# Main.net
KiCad netlist of a schematic drawn in EAGLE
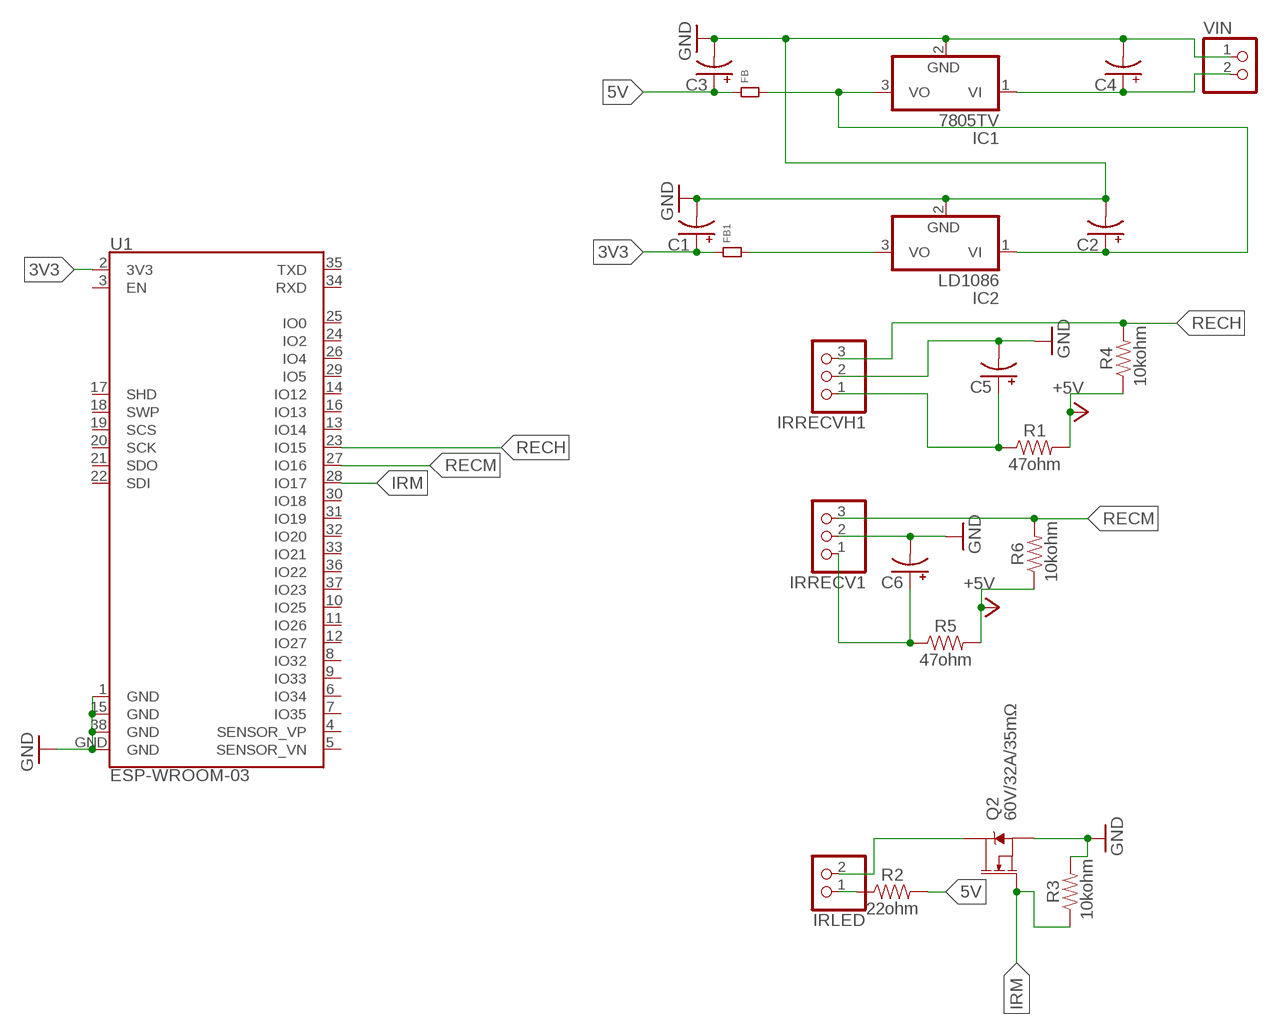
[diagram p0: schematic, sheet 1]

(export (version "E")
  (design (tool "Eeschema 10.0.6"))
  (components
    (comp (ref "C1")
      (value "CPOL-USE2-5")
      (footprint "eagle-import:E2-5")
      (libsource (lib "eagle-import") (part "CPOL-USE2-5"))
    )
    (comp (ref "C2")
      (value "CPOL-USE2-5")
      (footprint "eagle-import:E2-5")
      (libsource (lib "eagle-import") (part "CPOL-USE2-5"))
    )
    (comp (ref "C3")
      (value "CPOL-USE2-5")
      (footprint "eagle-import:E2-5")
      (libsource (lib "eagle-import") (part "CPOL-USE2-5"))
    )
    (comp (ref "C4")
      (value "CPOL-USE2-5")
      (footprint "eagle-import:E2-5")
      (libsource (lib "eagle-import") (part "CPOL-USE2-5"))
    )
    (comp (ref "C5")
      (value "CPOL-USE2-5")
      (footprint "eagle-import:E2-5")
      (libsource (lib "eagle-import") (part "CPOL-USE2-5"))
    )
    (comp (ref "C6")
      (value "CPOL-USE2-5")
      (footprint "eagle-import:E2-5")
      (libsource (lib "eagle-import") (part "CPOL-USE2-5"))
    )
    (comp (ref "FB")
      (value "RESISTOR.0603")
      (footprint "eagle-import:0603")
      (libsource (lib "eagle-import") (part "RESISTOR.0603"))
    )
    (comp (ref "FB1")
      (value "RESISTOR.0603")
      (footprint "eagle-import:0603")
      (libsource (lib "eagle-import") (part "RESISTOR.0603"))
    )
    (comp (ref "IC1")
      (value "7805TV")
      (footprint "eagle-import:TO220V")
      (libsource (lib "eagle-import") (part "78TV05"))
    )
    (comp (ref "IC2")
      (value "LD1086")
      (footprint "eagle-import:TO220V")
      (libsource (lib "eagle-import") (part "78TV05"))
    )
    (comp (ref "IRLED")
      (value "PINHD-1X2")
      (footprint "eagle-import:1X02")
      (libsource (lib "eagle-import") (part "PINHD-1X2"))
    )
    (comp (ref "IRRECV1")
      (value "PINHD-1X3")
      (footprint "eagle-import:1X03")
      (libsource (lib "eagle-import") (part "PINHD-1X3"))
    )
    (comp (ref "IRRECVH1")
      (value "PINHD-1X3")
      (footprint "eagle-import:1X03")
      (libsource (lib "eagle-import") (part "PINHD-1X3"))
    )
    (comp (ref "Q2")
      (value "60V/32A/35mΩ")
      (footprint "eagle-import:TO220V")
      (libsource (lib "eagle-import") (part "MOSFET-NCH-FQP30N06L"))
    )
    (comp (ref "R1")
      (value "47ohm")
      (footprint "eagle-import:AXIAL-0.3")
      (libsource (lib "eagle-import") (part "RESISTORAXIAL-0.3"))
    )
    (comp (ref "R2")
      (value "22ohm")
      (footprint "eagle-import:AXIAL-0.3")
      (libsource (lib "eagle-import") (part "RESISTORAXIAL-0.3"))
    )
    (comp (ref "R3")
      (value "10kohm")
      (footprint "eagle-import:AXIAL-0.3")
      (libsource (lib "eagle-import") (part "RESISTORAXIAL-0.3"))
    )
    (comp (ref "R4")
      (value "10kohm")
      (footprint "eagle-import:AXIAL-0.3")
      (libsource (lib "eagle-import") (part "RESISTORAXIAL-0.3"))
    )
    (comp (ref "R5")
      (value "47ohm")
      (footprint "eagle-import:AXIAL-0.3")
      (libsource (lib "eagle-import") (part "RESISTORAXIAL-0.3"))
    )
    (comp (ref "R6")
      (value "10kohm")
      (footprint "eagle-import:AXIAL-0.3")
      (libsource (lib "eagle-import") (part "RESISTORAXIAL-0.3"))
    )
    (comp (ref "U1")
      (value "ESP-WROOM-03")
      (footprint "eagle-import:ESP-WROOM-03")
      (libsource (lib "eagle-import") (part "ESP-WROOM-03"))
    )
    (comp (ref "VIN")
      (value "PINHD-1X2")
      (footprint "eagle-import:1X02")
      (libsource (lib "eagle-import") (part "PINHD-1X2"))
    )
  )
  (nets
    (net (code "1") (name "+5V") (class "Default")
      (node (ref "R1") (pin "P$2") (pinfunction "2_P$2") (pintype "passive"))
      (node (ref "R4") (pin "P$1") (pinfunction "1_P$1") (pintype "passive"))
      (node (ref "R5") (pin "P$2") (pinfunction "2_P$2") (pintype "passive"))
      (node (ref "R6") (pin "P$1") (pinfunction "1_P$1") (pintype "passive"))
    )
    (net (code "2") (name "3V3") (class "Default")
      (node (ref "C1") (pin "+") (pinfunction "+_+") (pintype "passive"))
      (node (ref "FB1") (pin "1") (pinfunction "1_1") (pintype "bidirectional"))
      (node (ref "U1") (pin "2") (pinfunction "3V3_2") (pintype "bidirectional"))
    )
    (net (code "3") (name "5V") (class "Default")
      (node (ref "C3") (pin "+") (pinfunction "+_+") (pintype "passive"))
      (node (ref "FB") (pin "1") (pinfunction "1_1") (pintype "bidirectional"))
      (node (ref "R2") (pin "P$2") (pinfunction "2_P$2") (pintype "passive"))
    )
    (net (code "4") (name "GND") (class "Default")
      (node (ref "C1") (pin "-") (pinfunction "-_-") (pintype "passive"))
      (node (ref "C2") (pin "-") (pinfunction "-_-") (pintype "passive"))
      (node (ref "C3") (pin "-") (pinfunction "-_-") (pintype "passive"))
      (node (ref "C4") (pin "-") (pinfunction "-_-") (pintype "passive"))
      (node (ref "C5") (pin "-") (pinfunction "-_-") (pintype "passive"))
      (node (ref "C6") (pin "-") (pinfunction "-_-") (pintype "passive"))
      (node (ref "IC1") (pin "2") (pinfunction "GND_2") (pintype "passive"))
      (node (ref "IC2") (pin "2") (pinfunction "GND_2") (pintype "passive"))
      (node (ref "IRRECV1") (pin "2") (pinfunction "2_2") (pintype "passive"))
      (node (ref "IRRECVH1") (pin "2") (pinfunction "2_2") (pintype "passive"))
      (node (ref "Q2") (pin "3") (pinfunction "S_3") (pintype "bidirectional"))
      (node (ref "R3") (pin "P$2") (pinfunction "2_P$2") (pintype "passive"))
      (node (ref "U1") (pin "1") (pinfunction "GND_1") (pintype "bidirectional"))
      (node (ref "U1") (pin "15") (pinfunction "GND_15") (pintype "bidirectional"))
      (node (ref "U1") (pin "38") (pinfunction "GND_38") (pintype "bidirectional"))
      (node (ref "U1") (pin "GND") (pinfunction "GND_GND") (pintype "bidirectional"))
      (node (ref "VIN") (pin "1") (pinfunction "1_1") (pintype "passive"))
    )
    (net (code "5") (name "IRM") (class "Default")
      (node (ref "Q2") (pin "1") (pinfunction "G_1") (pintype "bidirectional"))
      (node (ref "R3") (pin "P$1") (pinfunction "1_P$1") (pintype "passive"))
      (node (ref "U1") (pin "28") (pinfunction "IO17_28") (pintype "bidirectional"))
    )
    (net (code "6") (name "Net-(IC1-VI)") (class "Default")
      (node (ref "C4") (pin "+") (pinfunction "+_+") (pintype "passive"))
      (node (ref "IC1") (pin "1") (pinfunction "VI_1") (pintype "input"))
      (node (ref "VIN") (pin "2") (pinfunction "2_2") (pintype "passive"))
    )
    (net (code "7") (name "Net-(IC1-VO)") (class "Default")
      (node (ref "C2") (pin "+") (pinfunction "+_+") (pintype "passive"))
      (node (ref "FB") (pin "2") (pinfunction "2_2") (pintype "bidirectional"))
      (node (ref "IC1") (pin "3") (pinfunction "VO_3") (pintype "passive"))
      (node (ref "IC2") (pin "1") (pinfunction "VI_1") (pintype "input"))
    )
    (net (code "8") (name "Net-(IC2-VO)") (class "Default")
      (node (ref "FB1") (pin "2") (pinfunction "2_2") (pintype "bidirectional"))
      (node (ref "IC2") (pin "3") (pinfunction "VO_3") (pintype "passive"))
    )
    (net (code "9") (name "Net-(Q2-D)") (class "Default")
      (node (ref "IRLED") (pin "2") (pinfunction "2_2") (pintype "passive"))
      (node (ref "Q2") (pin "2") (pinfunction "D_2") (pintype "bidirectional"))
    )
    (net (code "10") (name "Net-(R1-1)") (class "Default")
      (node (ref "C5") (pin "+") (pinfunction "+_+") (pintype "passive"))
      (node (ref "IRRECVH1") (pin "1") (pinfunction "1_1") (pintype "passive"))
      (node (ref "R1") (pin "P$1") (pinfunction "1_P$1") (pintype "passive"))
    )
    (net (code "11") (name "Net-(R2-1)") (class "Default")
      (node (ref "IRLED") (pin "1") (pinfunction "1_1") (pintype "passive"))
      (node (ref "R2") (pin "P$1") (pinfunction "1_P$1") (pintype "passive"))
    )
    (net (code "12") (name "Net-(R5-1)") (class "Default")
      (node (ref "C6") (pin "+") (pinfunction "+_+") (pintype "passive"))
      (node (ref "IRRECV1") (pin "1") (pinfunction "1_1") (pintype "passive"))
      (node (ref "R5") (pin "P$1") (pinfunction "1_P$1") (pintype "passive"))
    )
    (net (code "13") (name "RECH") (class "Default")
      (node (ref "IRRECVH1") (pin "3") (pinfunction "3_3") (pintype "passive"))
      (node (ref "R4") (pin "P$2") (pinfunction "2_P$2") (pintype "passive"))
      (node (ref "U1") (pin "23") (pinfunction "IO15_23") (pintype "bidirectional"))
    )
    (net (code "14") (name "RECM") (class "Default")
      (node (ref "IRRECV1") (pin "3") (pinfunction "3_3") (pintype "passive"))
      (node (ref "R6") (pin "P$2") (pinfunction "2_P$2") (pintype "passive"))
      (node (ref "U1") (pin "27") (pinfunction "IO16_27") (pintype "bidirectional"))
    )
    (net (code "15") (name "unconnected-(U1-EN-Pad3)") (class "Default")
      (node (ref "U1") (pin "3") (pinfunction "EN_3") (pintype "bidirectional"))
    )
    (net (code "16") (name "unconnected-(U1-IO0-Pad25)") (class "Default")
      (node (ref "U1") (pin "25") (pinfunction "IO0_25") (pintype "bidirectional"))
    )
    (net (code "17") (name "unconnected-(U1-IO2-Pad24)") (class "Default")
      (node (ref "U1") (pin "24") (pinfunction "IO2_24") (pintype "bidirectional"))
    )
    (net (code "18") (name "unconnected-(U1-IO4-Pad26)") (class "Default")
      (node (ref "U1") (pin "26") (pinfunction "IO4_26") (pintype "bidirectional"))
    )
    (net (code "19") (name "unconnected-(U1-IO5-Pad29)") (class "Default")
      (node (ref "U1") (pin "29") (pinfunction "IO5_29") (pintype "bidirectional"))
    )
    (net (code "20") (name "unconnected-(U1-IO12-Pad14)") (class "Default")
      (node (ref "U1") (pin "14") (pinfunction "IO12_14") (pintype "bidirectional"))
    )
    (net (code "21") (name "unconnected-(U1-IO13-Pad16)") (class "Default")
      (node (ref "U1") (pin "16") (pinfunction "IO13_16") (pintype "bidirectional"))
    )
    (net (code "22") (name "unconnected-(U1-IO14-Pad13)") (class "Default")
      (node (ref "U1") (pin "13") (pinfunction "IO14_13") (pintype "bidirectional"))
    )
    (net (code "23") (name "unconnected-(U1-IO18-Pad30)") (class "Default")
      (node (ref "U1") (pin "30") (pinfunction "IO18_30") (pintype "bidirectional"))
    )
    (net (code "24") (name "unconnected-(U1-IO19-Pad31)") (class "Default")
      (node (ref "U1") (pin "31") (pinfunction "IO19_31") (pintype "bidirectional"))
    )
    (net (code "25") (name "unconnected-(U1-IO20-Pad32)") (class "Default")
      (node (ref "U1") (pin "32") (pinfunction "IO20_32") (pintype "bidirectional"))
    )
    (net (code "26") (name "unconnected-(U1-IO21-Pad33)") (class "Default")
      (node (ref "U1") (pin "33") (pinfunction "IO21_33") (pintype "bidirectional"))
    )
    (net (code "27") (name "unconnected-(U1-IO22-Pad36)") (class "Default")
      (node (ref "U1") (pin "36") (pinfunction "IO22_36") (pintype "bidirectional"))
    )
    (net (code "28") (name "unconnected-(U1-IO23-Pad37)") (class "Default")
      (node (ref "U1") (pin "37") (pinfunction "IO23_37") (pintype "bidirectional"))
    )
    (net (code "29") (name "unconnected-(U1-IO25-Pad10)") (class "Default")
      (node (ref "U1") (pin "10") (pinfunction "IO25_10") (pintype "bidirectional"))
    )
    (net (code "30") (name "unconnected-(U1-IO26-Pad11)") (class "Default")
      (node (ref "U1") (pin "11") (pinfunction "IO26_11") (pintype "bidirectional"))
    )
    (net (code "31") (name "unconnected-(U1-IO27-Pad12)") (class "Default")
      (node (ref "U1") (pin "12") (pinfunction "IO27_12") (pintype "bidirectional"))
    )
    (net (code "32") (name "unconnected-(U1-IO32-Pad8)") (class "Default")
      (node (ref "U1") (pin "8") (pinfunction "IO32_8") (pintype "bidirectional"))
    )
    (net (code "33") (name "unconnected-(U1-IO33-Pad9)") (class "Default")
      (node (ref "U1") (pin "9") (pinfunction "IO33_9") (pintype "bidirectional"))
    )
    (net (code "34") (name "unconnected-(U1-IO34-Pad6)") (class "Default")
      (node (ref "U1") (pin "6") (pinfunction "IO34_6") (pintype "bidirectional"))
    )
    (net (code "35") (name "unconnected-(U1-IO35-Pad7)") (class "Default")
      (node (ref "U1") (pin "7") (pinfunction "IO35_7") (pintype "bidirectional"))
    )
    (net (code "36") (name "unconnected-(U1-RXD-Pad34)") (class "Default")
      (node (ref "U1") (pin "34") (pinfunction "RXD_34") (pintype "bidirectional"))
    )
    (net (code "37") (name "unconnected-(U1-SCK-Pad20)") (class "Default")
      (node (ref "U1") (pin "20") (pinfunction "SCK_20") (pintype "bidirectional"))
    )
    (net (code "38") (name "unconnected-(U1-SCS-Pad19)") (class "Default")
      (node (ref "U1") (pin "19") (pinfunction "SCS_19") (pintype "bidirectional"))
    )
    (net (code "39") (name "unconnected-(U1-SDI-Pad22)") (class "Default")
      (node (ref "U1") (pin "22") (pinfunction "SDI_22") (pintype "bidirectional"))
    )
    (net (code "40") (name "unconnected-(U1-SDO-Pad21)") (class "Default")
      (node (ref "U1") (pin "21") (pinfunction "SDO_21") (pintype "bidirectional"))
    )
    (net (code "41") (name "unconnected-(U1-SENSOR_VN-Pad5)") (class "Default")
      (node (ref "U1") (pin "5") (pinfunction "SENSOR_VN_5") (pintype "bidirectional"))
    )
    (net (code "42") (name "unconnected-(U1-SENSOR_VP-Pad4)") (class "Default")
      (node (ref "U1") (pin "4") (pinfunction "SENSOR_VP_4") (pintype "bidirectional"))
    )
    (net (code "43") (name "unconnected-(U1-SHD-Pad17)") (class "Default")
      (node (ref "U1") (pin "17") (pinfunction "SHD_17") (pintype "bidirectional"))
    )
    (net (code "44") (name "unconnected-(U1-SWP-Pad18)") (class "Default")
      (node (ref "U1") (pin "18") (pinfunction "SWP_18") (pintype "bidirectional"))
    )
    (net (code "45") (name "unconnected-(U1-TXD-Pad35)") (class "Default")
      (node (ref "U1") (pin "35") (pinfunction "TXD_35") (pintype "bidirectional"))
    )
  )
)
